# Temperature.net
KiCad netlist of a schematic drawn in Altium Designer
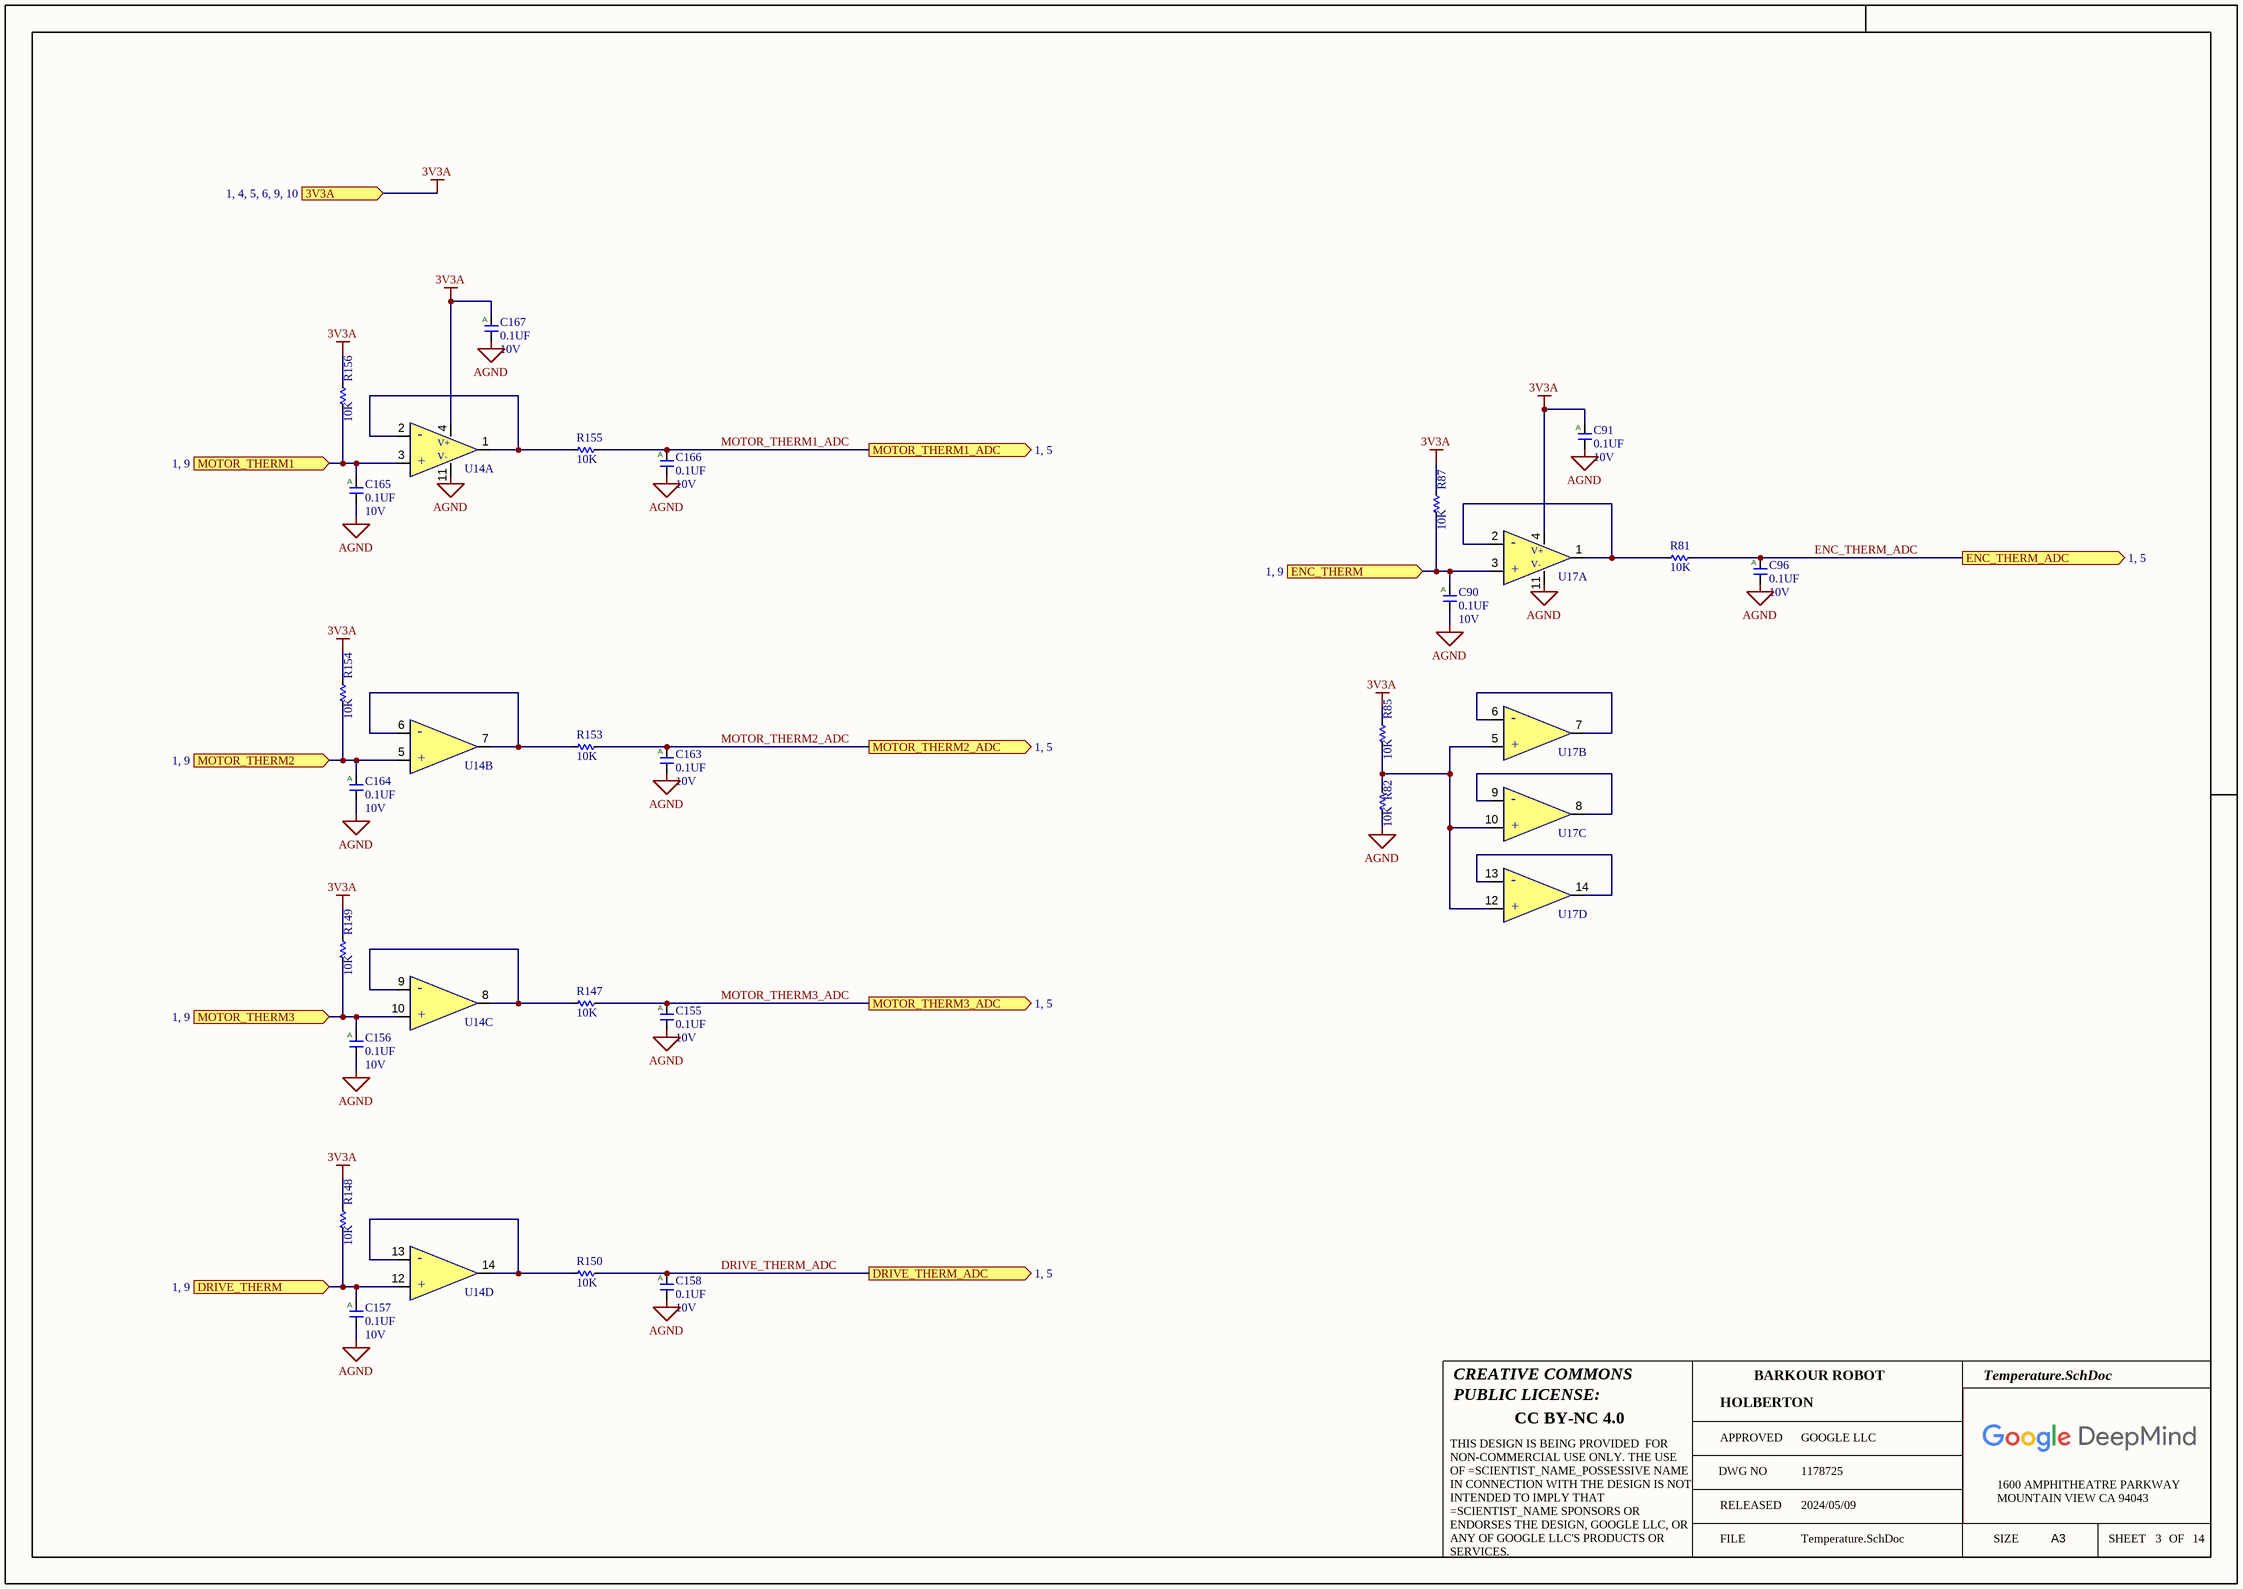
[diagram p0: Temperature.SchDoc]

(export (version "E")
  (design (tool "Eeschema 10.0.6"))
  (components
    (comp (ref "C90")
      (value "0.1UF")
      (footprint "C0201")
      (description "CAP, CER, X6S, 0.1uF, 10V, 10%, 0201, AUTOGRADE")
      (fields
        (field (name "MFG") "MURATA")
        (field (name "VOLTAGE") "10V")
        (field (name "Comment") "__Template_Cap_Auto")
      )
      (libsource (lib "AltiumReleaseLibDB") (part "__Template_Cap_Auto"))
    )
    (comp (ref "C91")
      (value "0.1UF")
      (footprint "C0201")
      (description "CAP, CER, X6S, 0.1uF, 10V, 10%, 0201, AUTOGRADE")
      (fields
        (field (name "MFG") "MURATA")
        (field (name "VOLTAGE") "10V")
        (field (name "Comment") "__Template_Cap_Auto")
      )
      (libsource (lib "AltiumReleaseLibDB") (part "__Template_Cap_Auto"))
    )
    (comp (ref "C96")
      (value "0.1UF")
      (footprint "C0201")
      (description "CAP, CER, X6S, 0.1uF, 10V, 10%, 0201, AUTOGRADE")
      (fields
        (field (name "MFG") "MURATA")
        (field (name "VOLTAGE") "10V")
        (field (name "Comment") "__Template_Cap_Auto")
      )
      (libsource (lib "AltiumReleaseLibDB") (part "__Template_Cap_Auto"))
    )
    (comp (ref "C155")
      (value "0.1UF")
      (footprint "C0201")
      (description "CAP, CER, X6S, 0.1uF, 10V, 10%, 0201, AUTOGRADE")
      (fields
        (field (name "MFG") "MURATA")
        (field (name "VOLTAGE") "10V")
        (field (name "Comment") "__Template_Cap_Auto")
      )
      (libsource (lib "AltiumReleaseLibDB") (part "__Template_Cap_Auto"))
    )
    (comp (ref "C156")
      (value "0.1UF")
      (footprint "C0201")
      (description "CAP, CER, X6S, 0.1uF, 10V, 10%, 0201, AUTOGRADE")
      (fields
        (field (name "MFG") "MURATA")
        (field (name "VOLTAGE") "10V")
        (field (name "Comment") "__Template_Cap_Auto")
      )
      (libsource (lib "AltiumReleaseLibDB") (part "__Template_Cap_Auto"))
    )
    (comp (ref "C157")
      (value "0.1UF")
      (footprint "C0201")
      (description "CAP, CER, X6S, 0.1uF, 10V, 10%, 0201, AUTOGRADE")
      (fields
        (field (name "MFG") "MURATA")
        (field (name "VOLTAGE") "10V")
        (field (name "Comment") "__Template_Cap_Auto")
      )
      (libsource (lib "AltiumReleaseLibDB") (part "__Template_Cap_Auto"))
    )
    (comp (ref "C158")
      (value "0.1UF")
      (footprint "C0201")
      (description "CAP, CER, X6S, 0.1uF, 10V, 10%, 0201, AUTOGRADE")
      (fields
        (field (name "MFG") "MURATA")
        (field (name "VOLTAGE") "10V")
        (field (name "Comment") "__Template_Cap_Auto")
      )
      (libsource (lib "AltiumReleaseLibDB") (part "__Template_Cap_Auto"))
    )
    (comp (ref "C163")
      (value "0.1UF")
      (footprint "C0201")
      (description "CAP, CER, X6S, 0.1uF, 10V, 10%, 0201, AUTOGRADE")
      (fields
        (field (name "MFG") "MURATA")
        (field (name "VOLTAGE") "10V")
        (field (name "Comment") "__Template_Cap_Auto")
      )
      (libsource (lib "AltiumReleaseLibDB") (part "__Template_Cap_Auto"))
    )
    (comp (ref "C164")
      (value "0.1UF")
      (footprint "C0201")
      (description "CAP, CER, X6S, 0.1uF, 10V, 10%, 0201, AUTOGRADE")
      (fields
        (field (name "MFG") "MURATA")
        (field (name "VOLTAGE") "10V")
        (field (name "Comment") "__Template_Cap_Auto")
      )
      (libsource (lib "AltiumReleaseLibDB") (part "__Template_Cap_Auto"))
    )
    (comp (ref "C165")
      (value "0.1UF")
      (footprint "C0201")
      (description "CAP, CER, X6S, 0.1uF, 10V, 10%, 0201, AUTOGRADE")
      (fields
        (field (name "MFG") "MURATA")
        (field (name "VOLTAGE") "10V")
        (field (name "Comment") "__Template_Cap_Auto")
      )
      (libsource (lib "AltiumReleaseLibDB") (part "__Template_Cap_Auto"))
    )
    (comp (ref "C166")
      (value "0.1UF")
      (footprint "C0201")
      (description "CAP, CER, X6S, 0.1uF, 10V, 10%, 0201, AUTOGRADE")
      (fields
        (field (name "MFG") "MURATA")
        (field (name "VOLTAGE") "10V")
        (field (name "Comment") "__Template_Cap_Auto")
      )
      (libsource (lib "AltiumReleaseLibDB") (part "__Template_Cap_Auto"))
    )
    (comp (ref "C167")
      (value "0.1UF")
      (footprint "C0201")
      (description "CAP, CER, X6S, 0.1uF, 10V, 10%, 0201, AUTOGRADE")
      (fields
        (field (name "MFG") "MURATA")
        (field (name "VOLTAGE") "10V")
        (field (name "Comment") "__Template_Cap_Auto")
      )
      (libsource (lib "AltiumReleaseLibDB") (part "__Template_Cap_Auto"))
    )
    (comp (ref "R81")
      (value "10K")
      (footprint "R0201")
      (description "RES, 10K, 1%, 1/20W, 0201, AUTOGRADE")
      (fields (field (name "MFG") "PANASONIC") (field (name "Comment") "__Template_Resistor"))
      (libsource (lib "AltiumReleaseLibDB") (part "__Template_Resistor"))
    )
    (comp (ref "R82")
      (value "10K")
      (footprint "R0201")
      (description "RES, 10K, 1%, 1/20W, 0201, AUTOGRADE")
      (fields (field (name "MFG") "PANASONIC") (field (name "Comment") "__Template_Resistor"))
      (libsource (lib "AltiumReleaseLibDB") (part "__Template_Resistor"))
    )
    (comp (ref "R85")
      (value "10K")
      (footprint "R0201")
      (description "RES, 10K, 1%, 1/20W, 0201, AUTOGRADE")
      (fields (field (name "MFG") "PANASONIC") (field (name "Comment") "__Template_Resistor"))
      (libsource (lib "AltiumReleaseLibDB") (part "__Template_Resistor"))
    )
    (comp (ref "R87")
      (value "10K")
      (footprint "R0201")
      (description "RES, 10K, 1%, 1/20W, 0201, AUTOGRADE")
      (fields (field (name "MFG") "PANASONIC") (field (name "Comment") "__Template_Resistor"))
      (libsource (lib "AltiumReleaseLibDB") (part "__Template_Resistor"))
    )
    (comp (ref "R147")
      (value "10K")
      (footprint "R0201")
      (description "RES, 10K, 1%, 1/20W, 0201, AUTOGRADE")
      (fields (field (name "MFG") "PANASONIC") (field (name "Comment") "__Template_Resistor"))
      (libsource (lib "AltiumReleaseLibDB") (part "__Template_Resistor"))
    )
    (comp (ref "R148")
      (value "10K")
      (footprint "R0201")
      (description "RES, 10K, 1%, 1/20W, 0201, AUTOGRADE")
      (fields (field (name "MFG") "PANASONIC") (field (name "Comment") "__Template_Resistor"))
      (libsource (lib "AltiumReleaseLibDB") (part "__Template_Resistor"))
    )
    (comp (ref "R149")
      (value "10K")
      (footprint "R0201")
      (description "RES, 10K, 1%, 1/20W, 0201, AUTOGRADE")
      (fields (field (name "MFG") "PANASONIC") (field (name "Comment") "__Template_Resistor"))
      (libsource (lib "AltiumReleaseLibDB") (part "__Template_Resistor"))
    )
    (comp (ref "R150")
      (value "10K")
      (footprint "R0201")
      (description "RES, 10K, 1%, 1/20W, 0201, AUTOGRADE")
      (fields (field (name "MFG") "PANASONIC") (field (name "Comment") "__Template_Resistor"))
      (libsource (lib "AltiumReleaseLibDB") (part "__Template_Resistor"))
    )
    (comp (ref "R153")
      (value "10K")
      (footprint "R0201")
      (description "RES, 10K, 1%, 1/20W, 0201, AUTOGRADE")
      (fields (field (name "MFG") "PANASONIC") (field (name "Comment") "__Template_Resistor"))
      (libsource (lib "AltiumReleaseLibDB") (part "__Template_Resistor"))
    )
    (comp (ref "R154")
      (value "10K")
      (footprint "R0201")
      (description "RES, 10K, 1%, 1/20W, 0201, AUTOGRADE")
      (fields (field (name "MFG") "PANASONIC") (field (name "Comment") "__Template_Resistor"))
      (libsource (lib "AltiumReleaseLibDB") (part "__Template_Resistor"))
    )
    (comp (ref "R155")
      (value "10K")
      (footprint "R0201")
      (description "RES, 10K, 1%, 1/20W, 0201, AUTOGRADE")
      (fields (field (name "MFG") "PANASONIC") (field (name "Comment") "__Template_Resistor"))
      (libsource (lib "AltiumReleaseLibDB") (part "__Template_Resistor"))
    )
    (comp (ref "R156")
      (value "10K")
      (footprint "R0201")
      (description "RES, 10K, 1%, 1/20W, 0201, AUTOGRADE")
      (fields (field (name "MFG") "PANASONIC") (field (name "Comment") "__Template_Resistor"))
      (libsource (lib "AltiumReleaseLibDB") (part "__Template_Resistor"))
    )
    (comp (ref "U14")
      (value "MCP6064")
      (footprint "14TSSOP65")
      (description "Microchip MCP6064-E/ST; Quad Op Amp; 0.73MHz CMOS; Rail to Rail; 3V; 5V; 14-Pin TSSOP")
      (fields (field (name "MFG") "Microchip Technology"))
      (libsource (lib "MiscSch1") (part "MICROCHIP_MCP6064"))
    )
    (comp (ref "U17")
      (value "MCP6064")
      (footprint "14TSSOP65")
      (description "Microchip MCP6064-E/ST; Quad Op Amp; 0.73MHz CMOS; Rail to Rail; 3V; 5V; 14-Pin TSSOP")
      (fields (field (name "MFG") "Microchip Technology"))
      (libsource (lib "MiscSch1") (part "MICROCHIP_MCP6064"))
    )
  )
  (nets
    (net (code "1") (name "/DRIVE_THERM") (class "Default")
      (node (ref "C157") (pin "1") (pintype "passive"))
      (node (ref "R148") (pin "1") (pintype "passive"))
      (node (ref "U14") (pin "12") (pinfunction "12_12") (pintype "passive"))
    )
    (net (code "2") (name "/DRIVE_THERM_ADC") (class "Default")
      (node (ref "C158") (pin "1") (pintype "passive"))
      (node (ref "R150") (pin "2") (pintype "passive"))
    )
    (net (code "3") (name "/ENC_THERM") (class "Default")
      (node (ref "C90") (pin "1") (pintype "passive"))
      (node (ref "R87") (pin "1") (pintype "passive"))
      (node (ref "U17") (pin "3") (pinfunction "3_3") (pintype "passive"))
    )
    (net (code "4") (name "/ENC_THERM_ADC") (class "Default")
      (node (ref "C96") (pin "1") (pintype "passive"))
      (node (ref "R81") (pin "2") (pintype "passive"))
    )
    (net (code "5") (name "/MOTOR_THERM1") (class "Default")
      (node (ref "C165") (pin "1") (pintype "passive"))
      (node (ref "R156") (pin "1") (pintype "passive"))
      (node (ref "U14") (pin "3") (pinfunction "3_3") (pintype "passive"))
    )
    (net (code "6") (name "/MOTOR_THERM1_ADC") (class "Default")
      (node (ref "C166") (pin "1") (pintype "passive"))
      (node (ref "R155") (pin "2") (pintype "passive"))
    )
    (net (code "7") (name "/MOTOR_THERM2") (class "Default")
      (node (ref "C164") (pin "1") (pintype "passive"))
      (node (ref "R154") (pin "1") (pintype "passive"))
      (node (ref "U14") (pin "5") (pinfunction "5_5") (pintype "passive"))
    )
    (net (code "8") (name "/MOTOR_THERM2_ADC") (class "Default")
      (node (ref "C163") (pin "1") (pintype "passive"))
      (node (ref "R153") (pin "2") (pintype "passive"))
    )
    (net (code "9") (name "/MOTOR_THERM3") (class "Default")
      (node (ref "C156") (pin "1") (pintype "passive"))
      (node (ref "R149") (pin "1") (pintype "passive"))
      (node (ref "U14") (pin "10") (pinfunction "10_10") (pintype "passive"))
    )
    (net (code "10") (name "/MOTOR_THERM3_ADC") (class "Default")
      (node (ref "C155") (pin "1") (pintype "passive"))
      (node (ref "R147") (pin "2") (pintype "passive"))
    )
    (net (code "11") (name "3V3A") (class "Default")
      (node (ref "C167") (pin "1") (pintype "passive"))
      (node (ref "C91") (pin "1") (pintype "passive"))
      (node (ref "R148") (pin "2") (pintype "passive"))
      (node (ref "R149") (pin "2") (pintype "passive"))
      (node (ref "R154") (pin "2") (pintype "passive"))
      (node (ref "R156") (pin "2") (pintype "passive"))
      (node (ref "R85") (pin "2") (pintype "passive"))
      (node (ref "R87") (pin "2") (pintype "passive"))
      (node (ref "U14") (pin "4") (pinfunction "4_4") (pintype "passive"))
      (node (ref "U17") (pin "4") (pinfunction "4_4") (pintype "passive"))
    )
    (net (code "12") (name "AGND") (class "Default")
      (node (ref "C155") (pin "2") (pintype "passive"))
      (node (ref "C156") (pin "2") (pintype "passive"))
      (node (ref "C157") (pin "2") (pintype "passive"))
      (node (ref "C158") (pin "2") (pintype "passive"))
      (node (ref "C163") (pin "2") (pintype "passive"))
      (node (ref "C164") (pin "2") (pintype "passive"))
      (node (ref "C165") (pin "2") (pintype "passive"))
      (node (ref "C166") (pin "2") (pintype "passive"))
      (node (ref "C167") (pin "2") (pintype "passive"))
      (node (ref "C90") (pin "2") (pintype "passive"))
      (node (ref "C91") (pin "2") (pintype "passive"))
      (node (ref "C96") (pin "2") (pintype "passive"))
      (node (ref "R82") (pin "1") (pintype "passive"))
      (node (ref "U14") (pin "11") (pinfunction "11_11") (pintype "passive"))
      (node (ref "U17") (pin "11") (pinfunction "11_11") (pintype "passive"))
    )
    (net (code "13") (name "Net-(R81-Pad1)") (class "Default")
      (node (ref "R81") (pin "1") (pintype "passive"))
      (node (ref "U17") (pin "1") (pinfunction "1_1") (pintype "passive"))
      (node (ref "U17") (pin "2") (pinfunction "2_2") (pintype "passive"))
    )
    (net (code "14") (name "Net-(R82-Pad2)") (class "Default")
      (node (ref "R82") (pin "2") (pintype "passive"))
      (node (ref "R85") (pin "1") (pintype "passive"))
      (node (ref "U17") (pin "10") (pinfunction "10_10") (pintype "passive"))
      (node (ref "U17") (pin "12") (pinfunction "12_12") (pintype "passive"))
      (node (ref "U17") (pin "5") (pinfunction "5_5") (pintype "passive"))
    )
    (net (code "15") (name "Net-(R147-Pad1)") (class "Default")
      (node (ref "R147") (pin "1") (pintype "passive"))
      (node (ref "U14") (pin "8") (pinfunction "8_8") (pintype "passive"))
      (node (ref "U14") (pin "9") (pinfunction "9_9") (pintype "passive"))
    )
    (net (code "16") (name "Net-(R150-Pad1)") (class "Default")
      (node (ref "R150") (pin "1") (pintype "passive"))
      (node (ref "U14") (pin "13") (pinfunction "13_13") (pintype "passive"))
      (node (ref "U14") (pin "14") (pinfunction "14_14") (pintype "passive"))
    )
    (net (code "17") (name "Net-(R153-Pad1)") (class "Default")
      (node (ref "R153") (pin "1") (pintype "passive"))
      (node (ref "U14") (pin "6") (pinfunction "6_6") (pintype "passive"))
      (node (ref "U14") (pin "7") (pinfunction "7_7") (pintype "passive"))
    )
    (net (code "18") (name "Net-(R155-Pad1)") (class "Default")
      (node (ref "R155") (pin "1") (pintype "passive"))
      (node (ref "U14") (pin "1") (pinfunction "1_1") (pintype "passive"))
      (node (ref "U14") (pin "2") (pinfunction "2_2") (pintype "passive"))
    )
    (net (code "19") (name "Net-(U17-Pad6)") (class "Default")
      (node (ref "U17") (pin "6") (pinfunction "6_6") (pintype "passive"))
      (node (ref "U17") (pin "7") (pinfunction "7_7") (pintype "passive"))
    )
    (net (code "20") (name "Net-(U17-Pad8)") (class "Default")
      (node (ref "U17") (pin "8") (pinfunction "8_8") (pintype "passive"))
      (node (ref "U17") (pin "9") (pinfunction "9_9") (pintype "passive"))
    )
    (net (code "21") (name "Net-(U17-Pad13)") (class "Default")
      (node (ref "U17") (pin "13") (pinfunction "13_13") (pintype "passive"))
      (node (ref "U17") (pin "14") (pinfunction "14_14") (pintype "passive"))
    )
  )
)
